# ESP32_MCU.net
KiCad netlist of a schematic drawn in Altium Designer
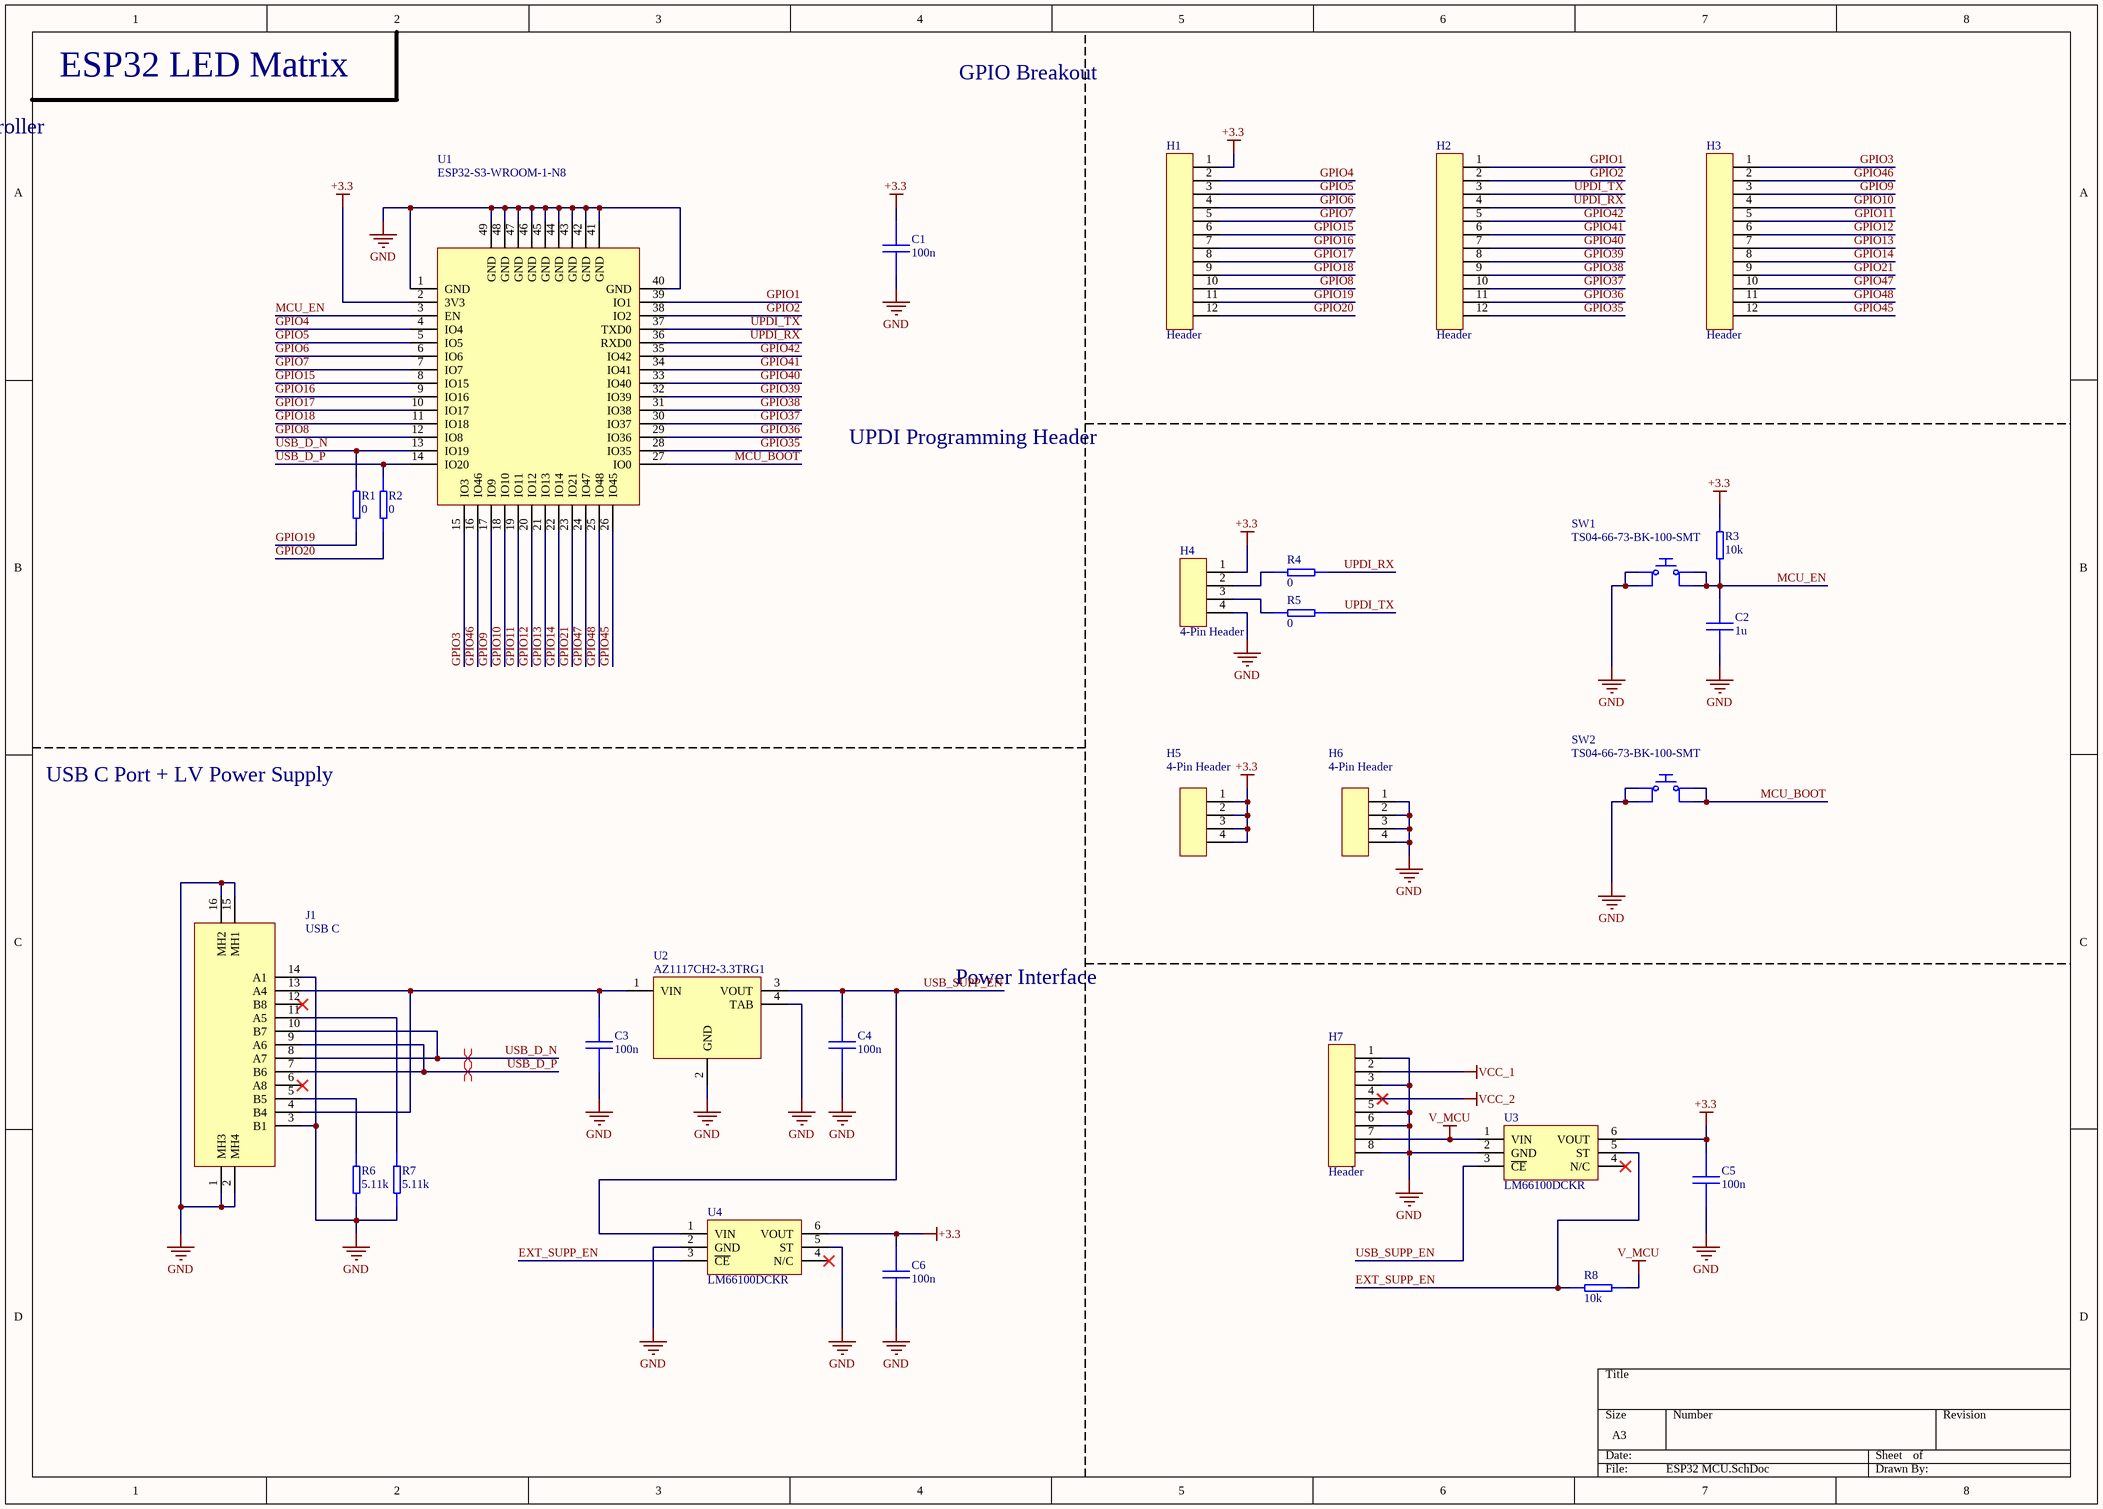
[diagram p0: ESP32 MCU.SchDoc]

(export (version "E")
  (design (tool "Eeschema 10.0.6"))
  (components
    (comp (ref "C1")
      (value "100n")
      (footprint "IEEE_Workshop_Footprints:CAP0805")
      (description "Non Polarized Capacitor")
      (libsource (lib "HT2.2") (part "Capacitor - Non Polarized"))
    )
    (comp (ref "C2")
      (value "1u")
      (footprint "IEEE_Workshop_Footprints:CAP0805")
      (description "Non Polarized Capacitor")
      (libsource (lib "HT2.2") (part "Capacitor - Non Polarized"))
    )
    (comp (ref "C3")
      (value "100n")
      (footprint "IEEE_Workshop_Footprints:CAP0805")
      (description "Non Polarized Capacitor")
      (libsource (lib "TD") (part "Capacitor - Non Polarized"))
    )
    (comp (ref "C4")
      (value "100n")
      (footprint "IEEE_Workshop_Footprints:CAP0805")
      (description "Non Polarized Capacitor")
      (libsource (lib "HT2.2") (part "Capacitor - Non Polarized"))
    )
    (comp (ref "C5")
      (value "100n")
      (footprint "IEEE_Workshop_Footprints:CAP0805")
      (description "Non Polarized Capacitor")
      (libsource (lib "HT2.2") (part "Capacitor - Non Polarized"))
    )
    (comp (ref "C6")
      (value "100n")
      (footprint "IEEE_Workshop_Footprints:CAP0805")
      (description "Non Polarized Capacitor")
      (libsource (lib "HT2.2") (part "Capacitor - Non Polarized"))
    )
    (comp (ref "H1")
      (value "Header")
      (footprint "IEEE_Workshop_Footprints:Header_1X12")
      (description "12-Pin Header")
      (libsource (lib "TD") (part "12-Pin Header"))
    )
    (comp (ref "H2")
      (value "Header")
      (footprint "IEEE_Workshop_Footprints:Header_1X12")
      (description "12-Pin Header")
      (libsource (lib "TD") (part "12-Pin Header"))
    )
    (comp (ref "H3")
      (value "Header")
      (footprint "IEEE_Workshop_Footprints:Header_1X12")
      (description "12-Pin Header")
      (libsource (lib "TD") (part "12-Pin Header"))
    )
    (comp (ref "H4")
      (value "4-Pin Header")
      (footprint "IEEE_Workshop_Footprints:Header_1X4")
      (libsource (lib "TD") (part "4-Pin Header"))
    )
    (comp (ref "H5")
      (value "4-Pin Header")
      (footprint "IEEE_Workshop_Footprints:Header_1X4")
      (libsource (lib "TD") (part "4-Pin Header"))
    )
    (comp (ref "H6")
      (value "4-Pin Header")
      (footprint "IEEE_Workshop_Footprints:Header_1X4")
      (libsource (lib "TD") (part "4-Pin Header"))
    )
    (comp (ref "H7")
      (value "Header")
      (footprint "IEEE_Workshop_Footprints:Header_1X8")
      (description "8-Pin Header")
      (libsource (lib "TD") (part "8-Pin Header"))
    )
    (comp (ref "J1")
      (value "USB C")
      (footprint "IEEE_Workshop_Footprints:USB TYPE C 12 PIN")
      (libsource (lib "TD") (part "USB Type C Connector 12 Pin"))
    )
    (comp (ref "R1")
      (value "0")
      (footprint "IEEE_Workshop_Footprints:RESC0805")
      (description "Resistor")
      (libsource (lib "TD") (part "Resistor"))
    )
    (comp (ref "R2")
      (value "0")
      (footprint "IEEE_Workshop_Footprints:RESC0805")
      (description "Resistor")
      (libsource (lib "TD") (part "Resistor"))
    )
    (comp (ref "R3")
      (value "10k")
      (footprint "IEEE_Workshop_Footprints:RESC0805")
      (description "Resistor")
      (libsource (lib "TD") (part "Resistor"))
    )
    (comp (ref "R4")
      (value "0")
      (footprint "IEEE_Workshop_Footprints:RESC0805")
      (description "Resistor")
      (libsource (lib "TD") (part "Resistor"))
    )
    (comp (ref "R5")
      (value "0")
      (footprint "IEEE_Workshop_Footprints:RESC0805")
      (description "Resistor")
      (libsource (lib "TD") (part "Resistor"))
    )
    (comp (ref "R6")
      (value "5.11k")
      (footprint "IEEE_Workshop_Footprints:RESC0805")
      (description "Resistor")
      (libsource (lib "HT2.2") (part "Resistor"))
    )
    (comp (ref "R7")
      (value "5.11k")
      (footprint "IEEE_Workshop_Footprints:RESC0805")
      (description "Resistor")
      (libsource (lib "HT2.2") (part "Resistor"))
    )
    (comp (ref "R8")
      (value "10k")
      (footprint "IEEE_Workshop_Footprints:RESC0805")
      (description "Resistor")
      (libsource (lib "TD") (part "Resistor"))
    )
    (comp (ref "SW1")
      (value "TS04-66-73-BK-100-SMT")
      (footprint "IEEE_Workshop_Footprints:Tactile Button 6.0mm x 6.0mm")
      (description "Switch")
      (fields (field (name "MOUSER PART NUMBER") "179-TS046673BK100SMT"))
      (libsource (lib "TD") (part "TS04-66-73-BK-100-SMT"))
    )
    (comp (ref "SW2")
      (value "TS04-66-73-BK-100-SMT")
      (footprint "IEEE_Workshop_Footprints:Tactile Button 6.0mm x 6.0mm")
      (description "Switch")
      (fields (field (name "MOUSER PART NUMBER") "179-TS046673BK100SMT"))
      (libsource (lib "TD") (part "TS04-66-73-BK-100-SMT"))
    )
    (comp (ref "U1")
      (value "ESP32-S3-WROOM-1-N8")
      (footprint "IEEE_Workshop_Footprints:ESP32-S3-WROOM-1-N8")
      (description "ESP32 Microcontroller with Bluetooth and Wifi")
      (libsource (lib "HT2.3") (part "ESP32-S3-WROOM-1-N8"))
    )
    (comp (ref "U2")
      (value "AZ1117CH2-3.3TRG1")
      (footprint "IEEE_Workshop_Footprints:SOT223")
      (description "3.3V Linear Voltage Regulator")
      (libsource (lib "TD") (part "AZ1117CH2-3.3TRG1_1"))
    )
    (comp (ref "U3")
      (value "LM66100DCKR")
      (footprint "IEEE_Workshop_Footprints:SC70-6")
      (description "5.5-V, 1.5-A 79-mΩ, Low IQ Ideal Diode With Input Polarity Protection")
      (fields (field (name "MOUSER PART NUMBER") "595-LM66100DCKR"))
      (libsource (lib "TD") (part "LM66100DCKR"))
    )
    (comp (ref "U4")
      (value "LM66100DCKR")
      (footprint "IEEE_Workshop_Footprints:SC70-6")
      (description "5.5-V, 1.5-A 79-mΩ, Low IQ Ideal Diode With Input Polarity Protection")
      (fields (field (name "MOUSER PART NUMBER") "595-LM66100DCKR"))
      (libsource (lib "TD") (part "LM66100DCKR"))
    )
  )
  (nets
    (net (code "1") (name "+3.3") (class "Default")
      (node (ref "C1") (pin "1") (pintype "passive"))
      (node (ref "C5") (pin "1") (pintype "passive"))
      (node (ref "C6") (pin "1") (pintype "passive"))
      (node (ref "H1") (pin "1") (pintype "passive"))
      (node (ref "H4") (pin "1") (pintype "passive"))
      (node (ref "H5") (pin "1") (pintype "passive"))
      (node (ref "H5") (pin "2") (pintype "passive"))
      (node (ref "H5") (pin "3") (pintype "passive"))
      (node (ref "H5") (pin "4") (pintype "passive"))
      (node (ref "R3") (pin "1") (pintype "passive"))
      (node (ref "U1") (pin "2") (pinfunction "3V3_2") (pintype "passive"))
      (node (ref "U3") (pin "6") (pinfunction "VOUT_6") (pintype "passive"))
      (node (ref "U4") (pin "6") (pinfunction "VOUT_6") (pintype "passive"))
    )
    (net (code "2") (name "/EXT_SUPP_EN") (class "Default")
      (node (ref "R8") (pin "1") (pintype "passive"))
      (node (ref "U3") (pin "5") (pinfunction "ST_5") (pintype "passive"))
      (node (ref "U4") (pin "3") (pinfunction "~{CE}_3") (pintype "passive"))
    )
    (net (code "3") (name "/GPIO1") (class "Default")
      (node (ref "H2") (pin "1") (pintype "passive"))
      (node (ref "U1") (pin "39") (pinfunction "IO1_39") (pintype "passive"))
    )
    (net (code "4") (name "/GPIO2") (class "Default")
      (node (ref "H2") (pin "2") (pintype "passive"))
      (node (ref "U1") (pin "38") (pinfunction "IO2_38") (pintype "passive"))
    )
    (net (code "5") (name "/GPIO3") (class "Default")
      (node (ref "H3") (pin "1") (pintype "passive"))
      (node (ref "U1") (pin "15") (pinfunction "IO3_15") (pintype "passive"))
    )
    (net (code "6") (name "/GPIO4") (class "Default")
      (node (ref "H1") (pin "2") (pintype "passive"))
      (node (ref "U1") (pin "4") (pinfunction "IO4_4") (pintype "passive"))
    )
    (net (code "7") (name "/GPIO5") (class "Default")
      (node (ref "H1") (pin "3") (pintype "passive"))
      (node (ref "U1") (pin "5") (pinfunction "IO5_5") (pintype "passive"))
    )
    (net (code "8") (name "/GPIO6") (class "Default")
      (node (ref "H1") (pin "4") (pintype "passive"))
      (node (ref "U1") (pin "6") (pinfunction "IO6_6") (pintype "passive"))
    )
    (net (code "9") (name "/GPIO7") (class "Default")
      (node (ref "H1") (pin "5") (pintype "passive"))
      (node (ref "U1") (pin "7") (pinfunction "IO7_7") (pintype "passive"))
    )
    (net (code "10") (name "/GPIO8") (class "Default")
      (node (ref "H1") (pin "10") (pintype "passive"))
      (node (ref "U1") (pin "12") (pinfunction "IO8_12") (pintype "passive"))
    )
    (net (code "11") (name "/GPIO9") (class "Default")
      (node (ref "H3") (pin "3") (pintype "passive"))
      (node (ref "U1") (pin "17") (pinfunction "IO9_17") (pintype "passive"))
    )
    (net (code "12") (name "/GPIO10") (class "Default")
      (node (ref "H3") (pin "4") (pintype "passive"))
      (node (ref "U1") (pin "18") (pinfunction "IO10_18") (pintype "passive"))
    )
    (net (code "13") (name "/GPIO11") (class "Default")
      (node (ref "H3") (pin "5") (pintype "passive"))
      (node (ref "U1") (pin "19") (pinfunction "IO11_19") (pintype "passive"))
    )
    (net (code "14") (name "/GPIO12") (class "Default")
      (node (ref "H3") (pin "6") (pintype "passive"))
      (node (ref "U1") (pin "20") (pinfunction "IO12_20") (pintype "passive"))
    )
    (net (code "15") (name "/GPIO13") (class "Default")
      (node (ref "H3") (pin "7") (pintype "passive"))
      (node (ref "U1") (pin "21") (pinfunction "IO13_21") (pintype "passive"))
    )
    (net (code "16") (name "/GPIO14") (class "Default")
      (node (ref "H3") (pin "8") (pintype "passive"))
      (node (ref "U1") (pin "22") (pinfunction "IO14_22") (pintype "passive"))
    )
    (net (code "17") (name "/GPIO15") (class "Default")
      (node (ref "H1") (pin "6") (pintype "passive"))
      (node (ref "U1") (pin "8") (pinfunction "IO15_8") (pintype "passive"))
    )
    (net (code "18") (name "/GPIO16") (class "Default")
      (node (ref "H1") (pin "7") (pintype "passive"))
      (node (ref "U1") (pin "9") (pinfunction "IO16_9") (pintype "passive"))
    )
    (net (code "19") (name "/GPIO17") (class "Default")
      (node (ref "H1") (pin "8") (pintype "passive"))
      (node (ref "U1") (pin "10") (pinfunction "IO17_10") (pintype "passive"))
    )
    (net (code "20") (name "/GPIO18") (class "Default")
      (node (ref "H1") (pin "9") (pintype "passive"))
      (node (ref "U1") (pin "11") (pinfunction "IO18_11") (pintype "passive"))
    )
    (net (code "21") (name "/GPIO19") (class "Default")
      (node (ref "H1") (pin "11") (pintype "passive"))
      (node (ref "R1") (pin "1") (pintype "passive"))
    )
    (net (code "22") (name "/GPIO20") (class "Default")
      (node (ref "H1") (pin "12") (pintype "passive"))
      (node (ref "R2") (pin "1") (pintype "passive"))
    )
    (net (code "23") (name "/GPIO21") (class "Default")
      (node (ref "H3") (pin "9") (pintype "passive"))
      (node (ref "U1") (pin "23") (pinfunction "IO21_23") (pintype "passive"))
    )
    (net (code "24") (name "/GPIO35") (class "Default")
      (node (ref "H2") (pin "12") (pintype "passive"))
      (node (ref "U1") (pin "28") (pinfunction "IO35_28") (pintype "passive"))
    )
    (net (code "25") (name "/GPIO36") (class "Default")
      (node (ref "H2") (pin "11") (pintype "passive"))
      (node (ref "U1") (pin "29") (pinfunction "IO36_29") (pintype "passive"))
    )
    (net (code "26") (name "/GPIO37") (class "Default")
      (node (ref "H2") (pin "10") (pintype "passive"))
      (node (ref "U1") (pin "30") (pinfunction "IO37_30") (pintype "passive"))
    )
    (net (code "27") (name "/GPIO38") (class "Default")
      (node (ref "H2") (pin "9") (pintype "passive"))
      (node (ref "U1") (pin "31") (pinfunction "IO38_31") (pintype "passive"))
    )
    (net (code "28") (name "/GPIO39") (class "Default")
      (node (ref "H2") (pin "8") (pintype "passive"))
      (node (ref "U1") (pin "32") (pinfunction "IO39_32") (pintype "passive"))
    )
    (net (code "29") (name "/GPIO40") (class "Default")
      (node (ref "H2") (pin "7") (pintype "passive"))
      (node (ref "U1") (pin "33") (pinfunction "IO40_33") (pintype "passive"))
    )
    (net (code "30") (name "/GPIO41") (class "Default")
      (node (ref "H2") (pin "6") (pintype "passive"))
      (node (ref "U1") (pin "34") (pinfunction "IO41_34") (pintype "passive"))
    )
    (net (code "31") (name "/GPIO42") (class "Default")
      (node (ref "H2") (pin "5") (pintype "passive"))
      (node (ref "U1") (pin "35") (pinfunction "IO42_35") (pintype "passive"))
    )
    (net (code "32") (name "/GPIO45") (class "Default")
      (node (ref "H3") (pin "12") (pintype "passive"))
      (node (ref "U1") (pin "26") (pinfunction "IO45_26") (pintype "passive"))
    )
    (net (code "33") (name "/GPIO46") (class "Default")
      (node (ref "H3") (pin "2") (pintype "passive"))
      (node (ref "U1") (pin "16") (pinfunction "IO46_16") (pintype "passive"))
    )
    (net (code "34") (name "/GPIO47") (class "Default")
      (node (ref "H3") (pin "10") (pintype "passive"))
      (node (ref "U1") (pin "24") (pinfunction "IO47_24") (pintype "passive"))
    )
    (net (code "35") (name "/GPIO48") (class "Default")
      (node (ref "H3") (pin "11") (pintype "passive"))
      (node (ref "U1") (pin "25") (pinfunction "IO48_25") (pintype "passive"))
    )
    (net (code "36") (name "/MCU_BOOT") (class "Default")
      (node (ref "SW2") (pin "3") (pintype "passive"))
      (node (ref "SW2") (pin "4") (pintype "passive"))
      (node (ref "U1") (pin "27") (pinfunction "IO0_27") (pintype "passive"))
    )
    (net (code "37") (name "/MCU_EN") (class "Default")
      (node (ref "C2") (pin "1") (pintype "passive"))
      (node (ref "R3") (pin "2") (pintype "passive"))
      (node (ref "SW1") (pin "3") (pintype "passive"))
      (node (ref "SW1") (pin "4") (pintype "passive"))
      (node (ref "U1") (pin "3") (pinfunction "EN_3") (pintype "passive"))
    )
    (net (code "38") (name "/UPDI_RX") (class "Default")
      (node (ref "H2") (pin "4") (pintype "passive"))
      (node (ref "R4") (pin "1") (pintype "passive"))
      (node (ref "U1") (pin "36") (pinfunction "RXD0_36") (pintype "passive"))
    )
    (net (code "39") (name "/UPDI_TX") (class "Default")
      (node (ref "H2") (pin "3") (pintype "passive"))
      (node (ref "R5") (pin "1") (pintype "passive"))
      (node (ref "U1") (pin "37") (pinfunction "TXD0_37") (pintype "passive"))
    )
    (net (code "40") (name "/USB_D_N") (class "Default")
      (node (ref "J1") (pin "10") (pinfunction "B7_10") (pintype "passive"))
      (node (ref "J1") (pin "8") (pinfunction "A7_8") (pintype "passive"))
      (node (ref "R1") (pin "2") (pintype "passive"))
      (node (ref "U1") (pin "13") (pinfunction "IO19_13") (pintype "passive"))
    )
    (net (code "41") (name "/USB_D_P") (class "Default")
      (node (ref "J1") (pin "7") (pinfunction "B6_7") (pintype "passive"))
      (node (ref "J1") (pin "9") (pinfunction "A6_9") (pintype "passive"))
      (node (ref "R2") (pin "2") (pintype "passive"))
      (node (ref "U1") (pin "14") (pinfunction "IO20_14") (pintype "passive"))
    )
    (net (code "42") (name "/USB_SUPP_EN") (class "Default")
      (node (ref "C4") (pin "1") (pintype "passive"))
      (node (ref "U2") (pin "3") (pinfunction "VOUT_3") (pintype "passive"))
      (node (ref "U3") (pin "3") (pinfunction "~{CE}_3") (pintype "passive"))
      (node (ref "U4") (pin "1") (pinfunction "VIN_1") (pintype "passive"))
    )
    (net (code "43") (name "GND") (class "Default")
      (node (ref "C1") (pin "2") (pintype "passive"))
      (node (ref "C2") (pin "2") (pintype "passive"))
      (node (ref "C3") (pin "2") (pintype "passive"))
      (node (ref "C4") (pin "2") (pintype "passive"))
      (node (ref "C5") (pin "2") (pintype "passive"))
      (node (ref "C6") (pin "2") (pintype "passive"))
      (node (ref "H4") (pin "4") (pintype "passive"))
      (node (ref "H6") (pin "1") (pintype "passive"))
      (node (ref "H6") (pin "2") (pintype "passive"))
      (node (ref "H6") (pin "3") (pintype "passive"))
      (node (ref "H6") (pin "4") (pintype "passive"))
      (node (ref "H7") (pin "1") (pintype "passive"))
      (node (ref "H7") (pin "3") (pintype "passive"))
      (node (ref "H7") (pin "5") (pintype "passive"))
      (node (ref "H7") (pin "6") (pintype "passive"))
      (node (ref "H7") (pin "8") (pintype "passive"))
      (node (ref "J1") (pin "1") (pinfunction "MH3_1") (pintype "passive"))
      (node (ref "J1") (pin "14") (pinfunction "A1_14") (pintype "passive"))
      (node (ref "J1") (pin "15") (pinfunction "MH1_15") (pintype "passive"))
      (node (ref "J1") (pin "16") (pinfunction "MH2_16") (pintype "passive"))
      (node (ref "J1") (pin "2") (pinfunction "MH4_2") (pintype "passive"))
      (node (ref "J1") (pin "3") (pinfunction "B1_3") (pintype "passive"))
      (node (ref "R6") (pin "1") (pintype "passive"))
      (node (ref "R7") (pin "1") (pintype "passive"))
      (node (ref "SW1") (pin "1") (pintype "passive"))
      (node (ref "SW1") (pin "2") (pintype "passive"))
      (node (ref "SW2") (pin "1") (pintype "passive"))
      (node (ref "SW2") (pin "2") (pintype "passive"))
      (node (ref "U1") (pin "1") (pinfunction "GND_1") (pintype "passive"))
      (node (ref "U1") (pin "40") (pinfunction "GND_40") (pintype "passive"))
      (node (ref "U1") (pin "41") (pinfunction "GND_41") (pintype "passive"))
      (node (ref "U1") (pin "42") (pinfunction "GND_42") (pintype "passive"))
      (node (ref "U1") (pin "43") (pinfunction "GND_43") (pintype "passive"))
      (node (ref "U1") (pin "44") (pinfunction "GND_44") (pintype "passive"))
      (node (ref "U1") (pin "45") (pinfunction "GND_45") (pintype "passive"))
      (node (ref "U1") (pin "46") (pinfunction "GND_46") (pintype "passive"))
      (node (ref "U1") (pin "47") (pinfunction "GND_47") (pintype "passive"))
      (node (ref "U1") (pin "48") (pinfunction "GND_48") (pintype "passive"))
      (node (ref "U1") (pin "49") (pinfunction "GND_49") (pintype "passive"))
      (node (ref "U2") (pin "2") (pinfunction "GND_2") (pintype "passive"))
      (node (ref "U2") (pin "4") (pinfunction "TAB_4") (pintype "passive"))
      (node (ref "U3") (pin "2") (pinfunction "GND_2") (pintype "passive"))
      (node (ref "U4") (pin "2") (pinfunction "GND_2") (pintype "passive"))
      (node (ref "U4") (pin "5") (pinfunction "ST_5") (pintype "passive"))
    )
    (net (code "44") (name "Net-(H4-Pad2)") (class "Default")
      (node (ref "H4") (pin "2") (pintype "passive"))
      (node (ref "R4") (pin "2") (pintype "passive"))
    )
    (net (code "45") (name "Net-(H4-Pad3)") (class "Default")
      (node (ref "H4") (pin "3") (pintype "passive"))
      (node (ref "R5") (pin "2") (pintype "passive"))
    )
    (net (code "46") (name "Net-(J1-A4)") (class "Default")
      (node (ref "C3") (pin "1") (pintype "passive"))
      (node (ref "J1") (pin "13") (pinfunction "A4_13") (pintype "passive"))
      (node (ref "J1") (pin "4") (pinfunction "B4_4") (pintype "passive"))
      (node (ref "U2") (pin "1") (pinfunction "VIN_1") (pintype "passive"))
    )
    (net (code "47") (name "Net-(J1-A5)") (class "Default")
      (node (ref "J1") (pin "11") (pinfunction "A5_11") (pintype "passive"))
      (node (ref "R7") (pin "2") (pintype "passive"))
    )
    (net (code "48") (name "Net-(J1-B5)") (class "Default")
      (node (ref "J1") (pin "5") (pinfunction "B5_5") (pintype "passive"))
      (node (ref "R6") (pin "2") (pintype "passive"))
    )
    (net (code "49") (name "VCC_1") (class "Default") (node (ref "H7") (pin "2") (pintype "passive")))
    (net (code "50") (name "VCC_2") (class "Default") (node (ref "H7") (pin "4") (pintype "passive")))
    (net (code "51") (name "V_MCU") (class "Default")
      (node (ref "H7") (pin "7") (pintype "passive"))
      (node (ref "R8") (pin "2") (pintype "passive"))
      (node (ref "U3") (pin "1") (pinfunction "VIN_1") (pintype "passive"))
    )
    (net (code "52") (name "unconnected-(J1-A8-Pad6)") (class "Default")
      (node (ref "J1") (pin "6") (pinfunction "A8_6") (pintype "passive+no_connect"))
    )
    (net (code "53") (name "unconnected-(J1-B8-Pad12)") (class "Default")
      (node (ref "J1") (pin "12") (pinfunction "B8_12") (pintype "passive+no_connect"))
    )
    (net (code "54") (name "unconnected-(U3-N{slash}C-Pad4)") (class "Default")
      (node (ref "U3") (pin "4") (pinfunction "N/C_4") (pintype "passive+no_connect"))
    )
    (net (code "55") (name "unconnected-(U4-N{slash}C-Pad4)") (class "Default")
      (node (ref "U4") (pin "4") (pinfunction "N/C_4") (pintype "passive+no_connect"))
    )
  )
)
